# Bus_Definition_V1_2.net
KiCad netlist of a schematic drawn in EAGLE
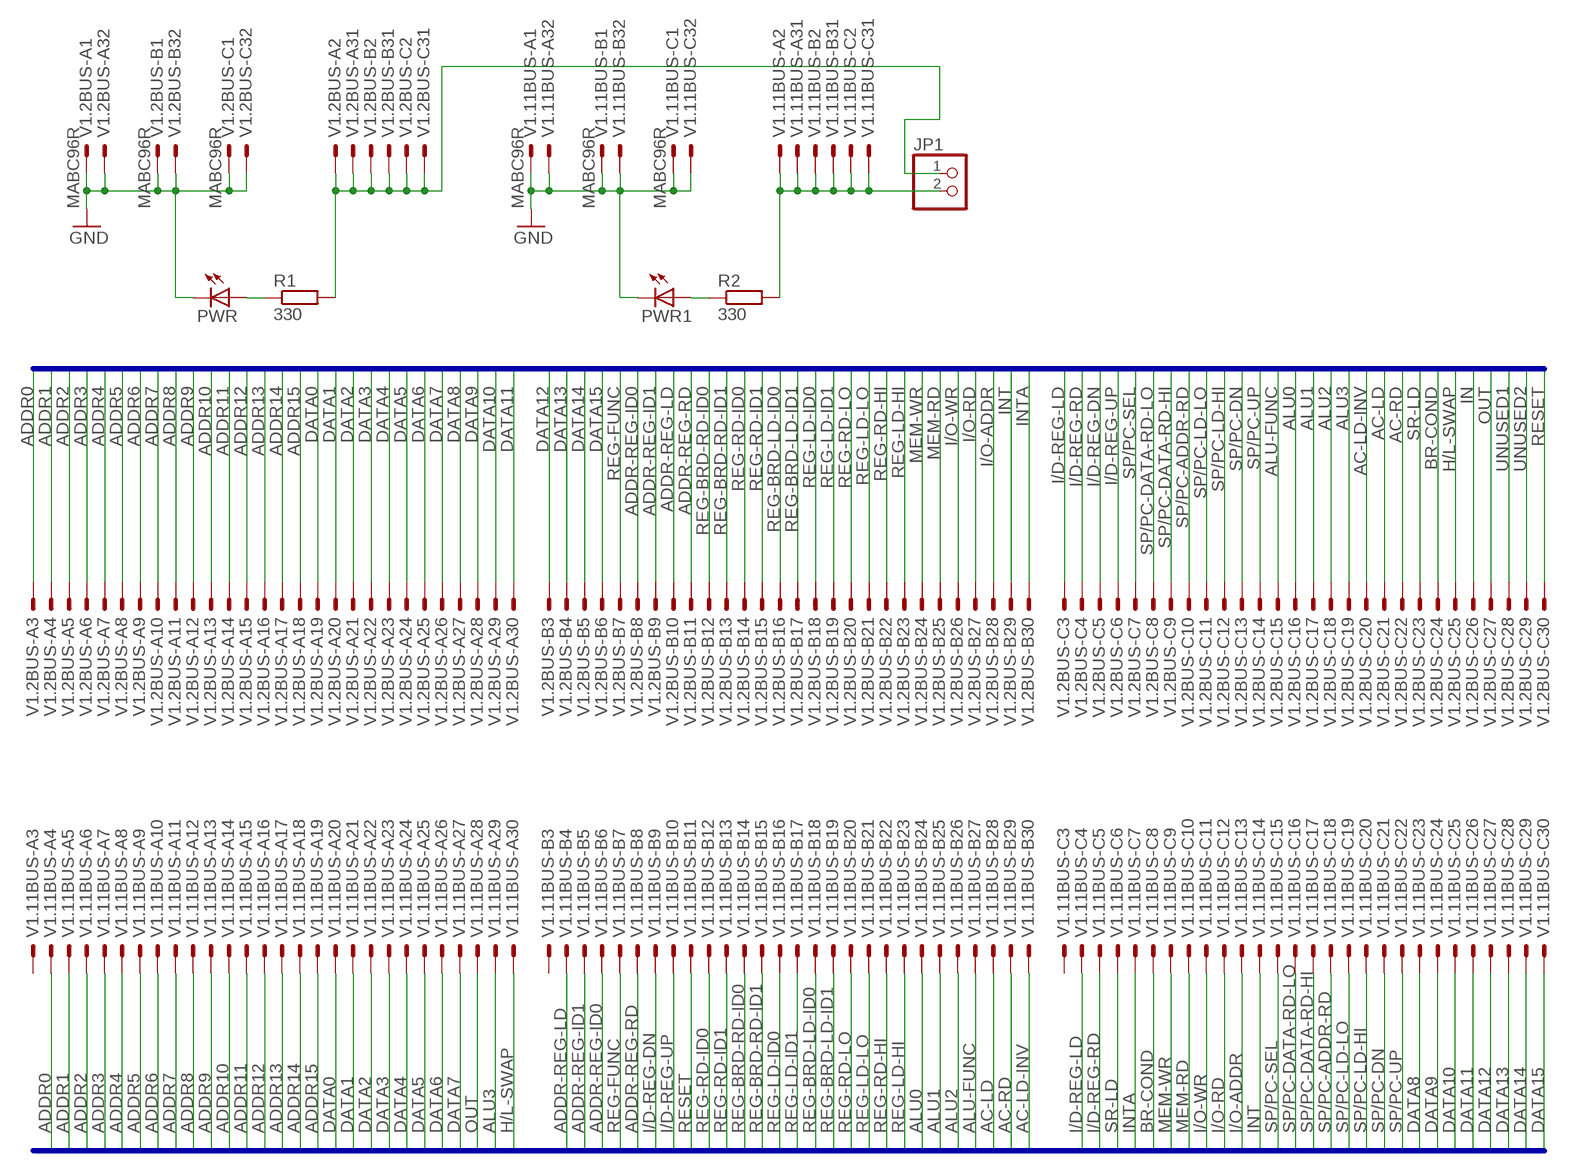
[diagram p0: schematic, sheet 1]

(export (version "E")
  (design (tool "Eeschema 10.0.6"))
  (components
    (comp (ref "JP1")
      (value "PINHD-1X2")
      (footprint "eagle-import:1X02")
      (libsource (lib "eagle-import") (part "PINHD-1X2"))
    )
    (comp (ref "PWR")
      (value "LED5MM")
      (footprint "eagle-import:LED5MM")
      (libsource (lib "eagle-import") (part "LED5MM"))
    )
    (comp (ref "PWR1")
      (value "LED5MM")
      (footprint "eagle-import:LED5MM")
      (libsource (lib "eagle-import") (part "LED5MM"))
    )
    (comp (ref "R1")
      (value "330")
      (footprint "eagle-import:0207_10")
      (libsource (lib "eagle-import") (part "R0207/10"))
    )
    (comp (ref "R2")
      (value "330")
      (footprint "eagle-import:0207_10")
      (libsource (lib "eagle-import") (part "R0207/10"))
    )
    (comp (ref "V1.2BUS")
      (value "MABC96R")
      (footprint "eagle-import:MABC96R")
      (libsource (lib "eagle-import") (part "MABC96R"))
    )
    (comp (ref "V1.11BUS")
      (value "MABC96R")
      (footprint "eagle-import:MABC96R")
      (libsource (lib "eagle-import") (part "MABC96R"))
    )
  )
  (nets
    (net (code "1") (name "/AC-LD") (class "Default")
      (node (ref "V1.11BUS") (pin "B28") (pinfunction "S_B28") (pintype "passive"))
      (node (ref "V1.2BUS") (pin "C21") (pinfunction "S_C21") (pintype "passive"))
    )
    (net (code "2") (name "/AC-LD-INV") (class "Default")
      (node (ref "V1.11BUS") (pin "B30") (pinfunction "S_B30") (pintype "passive"))
      (node (ref "V1.2BUS") (pin "C20") (pinfunction "S_C20") (pintype "passive"))
    )
    (net (code "3") (name "/AC-RD") (class "Default")
      (node (ref "V1.11BUS") (pin "B29") (pinfunction "S_B29") (pintype "passive"))
      (node (ref "V1.2BUS") (pin "C22") (pinfunction "S_C22") (pintype "passive"))
    )
    (net (code "4") (name "/ADDR-REG-ID0") (class "Default")
      (node (ref "V1.11BUS") (pin "B6") (pinfunction "S_B6") (pintype "passive"))
      (node (ref "V1.2BUS") (pin "B8") (pinfunction "S_B8") (pintype "passive"))
    )
    (net (code "5") (name "/ADDR-REG-ID1") (class "Default")
      (node (ref "V1.11BUS") (pin "B5") (pinfunction "S_B5") (pintype "passive"))
      (node (ref "V1.2BUS") (pin "B9") (pinfunction "S_B9") (pintype "passive"))
    )
    (net (code "6") (name "/ADDR-REG-LD") (class "Default")
      (node (ref "V1.11BUS") (pin "B4") (pinfunction "S_B4") (pintype "passive"))
      (node (ref "V1.2BUS") (pin "B10") (pinfunction "S_B10") (pintype "passive"))
    )
    (net (code "7") (name "/ADDR-REG-RD") (class "Default")
      (node (ref "V1.11BUS") (pin "B8") (pinfunction "S_B8") (pintype "passive"))
      (node (ref "V1.2BUS") (pin "B11") (pinfunction "S_B11") (pintype "passive"))
    )
    (net (code "8") (name "/ADDR0") (class "Default")
      (node (ref "V1.11BUS") (pin "A4") (pinfunction "S_A4") (pintype "passive"))
      (node (ref "V1.2BUS") (pin "A3") (pinfunction "S_A3") (pintype "passive"))
    )
    (net (code "9") (name "/ADDR1") (class "Default")
      (node (ref "V1.11BUS") (pin "A5") (pinfunction "S_A5") (pintype "passive"))
      (node (ref "V1.2BUS") (pin "A4") (pinfunction "S_A4") (pintype "passive"))
    )
    (net (code "10") (name "/ADDR2") (class "Default")
      (node (ref "V1.11BUS") (pin "A6") (pinfunction "S_A6") (pintype "passive"))
      (node (ref "V1.2BUS") (pin "A5") (pinfunction "S_A5") (pintype "passive"))
    )
    (net (code "11") (name "/ADDR3") (class "Default")
      (node (ref "V1.11BUS") (pin "A7") (pinfunction "S_A7") (pintype "passive"))
      (node (ref "V1.2BUS") (pin "A6") (pinfunction "S_A6") (pintype "passive"))
    )
    (net (code "12") (name "/ADDR4") (class "Default")
      (node (ref "V1.11BUS") (pin "A8") (pinfunction "S_A8") (pintype "passive"))
      (node (ref "V1.2BUS") (pin "A7") (pinfunction "S_A7") (pintype "passive"))
    )
    (net (code "13") (name "/ADDR5") (class "Default")
      (node (ref "V1.11BUS") (pin "A9") (pinfunction "S_A9") (pintype "passive"))
      (node (ref "V1.2BUS") (pin "A8") (pinfunction "S_A8") (pintype "passive"))
    )
    (net (code "14") (name "/ADDR6") (class "Default")
      (node (ref "V1.11BUS") (pin "A10") (pinfunction "S_A10") (pintype "passive"))
      (node (ref "V1.2BUS") (pin "A9") (pinfunction "S_A9") (pintype "passive"))
    )
    (net (code "15") (name "/ADDR7") (class "Default")
      (node (ref "V1.11BUS") (pin "A11") (pinfunction "S_A11") (pintype "passive"))
      (node (ref "V1.2BUS") (pin "A10") (pinfunction "S_A10") (pintype "passive"))
    )
    (net (code "16") (name "/ADDR8") (class "Default")
      (node (ref "V1.11BUS") (pin "A12") (pinfunction "S_A12") (pintype "passive"))
      (node (ref "V1.2BUS") (pin "A11") (pinfunction "S_A11") (pintype "passive"))
    )
    (net (code "17") (name "/ADDR9") (class "Default")
      (node (ref "V1.11BUS") (pin "A13") (pinfunction "S_A13") (pintype "passive"))
      (node (ref "V1.2BUS") (pin "A12") (pinfunction "S_A12") (pintype "passive"))
    )
    (net (code "18") (name "/ADDR10") (class "Default")
      (node (ref "V1.11BUS") (pin "A14") (pinfunction "S_A14") (pintype "passive"))
      (node (ref "V1.2BUS") (pin "A13") (pinfunction "S_A13") (pintype "passive"))
    )
    (net (code "19") (name "/ADDR11") (class "Default")
      (node (ref "V1.11BUS") (pin "A15") (pinfunction "S_A15") (pintype "passive"))
      (node (ref "V1.2BUS") (pin "A14") (pinfunction "S_A14") (pintype "passive"))
    )
    (net (code "20") (name "/ADDR12") (class "Default")
      (node (ref "V1.11BUS") (pin "A16") (pinfunction "S_A16") (pintype "passive"))
      (node (ref "V1.2BUS") (pin "A15") (pinfunction "S_A15") (pintype "passive"))
    )
    (net (code "21") (name "/ADDR13") (class "Default")
      (node (ref "V1.11BUS") (pin "A17") (pinfunction "S_A17") (pintype "passive"))
      (node (ref "V1.2BUS") (pin "A16") (pinfunction "S_A16") (pintype "passive"))
    )
    (net (code "22") (name "/ADDR14") (class "Default")
      (node (ref "V1.11BUS") (pin "A18") (pinfunction "S_A18") (pintype "passive"))
      (node (ref "V1.2BUS") (pin "A17") (pinfunction "S_A17") (pintype "passive"))
    )
    (net (code "23") (name "/ADDR15") (class "Default")
      (node (ref "V1.11BUS") (pin "A19") (pinfunction "S_A19") (pintype "passive"))
      (node (ref "V1.2BUS") (pin "A18") (pinfunction "S_A18") (pintype "passive"))
    )
    (net (code "24") (name "/ALU-FUNC") (class "Default")
      (node (ref "V1.11BUS") (pin "B27") (pinfunction "S_B27") (pintype "passive"))
      (node (ref "V1.2BUS") (pin "C15") (pinfunction "S_C15") (pintype "passive"))
    )
    (net (code "25") (name "/ALU0") (class "Default")
      (node (ref "V1.11BUS") (pin "B24") (pinfunction "S_B24") (pintype "passive"))
      (node (ref "V1.2BUS") (pin "C16") (pinfunction "S_C16") (pintype "passive"))
    )
    (net (code "26") (name "/ALU1") (class "Default")
      (node (ref "V1.11BUS") (pin "B25") (pinfunction "S_B25") (pintype "passive"))
      (node (ref "V1.2BUS") (pin "C17") (pinfunction "S_C17") (pintype "passive"))
    )
    (net (code "27") (name "/ALU2") (class "Default")
      (node (ref "V1.11BUS") (pin "B26") (pinfunction "S_B26") (pintype "passive"))
      (node (ref "V1.2BUS") (pin "C18") (pinfunction "S_C18") (pintype "passive"))
    )
    (net (code "28") (name "/ALU3") (class "Default")
      (node (ref "V1.11BUS") (pin "A29") (pinfunction "S_A29") (pintype "passive"))
      (node (ref "V1.2BUS") (pin "C19") (pinfunction "S_C19") (pintype "passive"))
    )
    (net (code "29") (name "/BR-COND") (class "Default")
      (node (ref "V1.11BUS") (pin "C8") (pinfunction "S_C8") (pintype "passive"))
      (node (ref "V1.2BUS") (pin "C24") (pinfunction "S_C24") (pintype "passive"))
    )
    (net (code "30") (name "/DATA0") (class "Default")
      (node (ref "V1.11BUS") (pin "A20") (pinfunction "S_A20") (pintype "passive"))
      (node (ref "V1.2BUS") (pin "A19") (pinfunction "S_A19") (pintype "passive"))
    )
    (net (code "31") (name "/DATA1") (class "Default")
      (node (ref "V1.11BUS") (pin "A21") (pinfunction "S_A21") (pintype "passive"))
      (node (ref "V1.2BUS") (pin "A20") (pinfunction "S_A20") (pintype "passive"))
    )
    (net (code "32") (name "/DATA2") (class "Default")
      (node (ref "V1.11BUS") (pin "A22") (pinfunction "S_A22") (pintype "passive"))
      (node (ref "V1.2BUS") (pin "A21") (pinfunction "S_A21") (pintype "passive"))
    )
    (net (code "33") (name "/DATA3") (class "Default")
      (node (ref "V1.11BUS") (pin "A23") (pinfunction "S_A23") (pintype "passive"))
      (node (ref "V1.2BUS") (pin "A22") (pinfunction "S_A22") (pintype "passive"))
    )
    (net (code "34") (name "/DATA4") (class "Default")
      (node (ref "V1.11BUS") (pin "A24") (pinfunction "S_A24") (pintype "passive"))
      (node (ref "V1.2BUS") (pin "A23") (pinfunction "S_A23") (pintype "passive"))
    )
    (net (code "35") (name "/DATA5") (class "Default")
      (node (ref "V1.11BUS") (pin "A25") (pinfunction "S_A25") (pintype "passive"))
      (node (ref "V1.2BUS") (pin "A24") (pinfunction "S_A24") (pintype "passive"))
    )
    (net (code "36") (name "/DATA6") (class "Default")
      (node (ref "V1.11BUS") (pin "A26") (pinfunction "S_A26") (pintype "passive"))
      (node (ref "V1.2BUS") (pin "A25") (pinfunction "S_A25") (pintype "passive"))
    )
    (net (code "37") (name "/DATA7") (class "Default")
      (node (ref "V1.11BUS") (pin "A27") (pinfunction "S_A27") (pintype "passive"))
      (node (ref "V1.2BUS") (pin "A26") (pinfunction "S_A26") (pintype "passive"))
    )
    (net (code "38") (name "/DATA8") (class "Default")
      (node (ref "V1.11BUS") (pin "C23") (pinfunction "S_C23") (pintype "passive"))
      (node (ref "V1.2BUS") (pin "A27") (pinfunction "S_A27") (pintype "passive"))
    )
    (net (code "39") (name "/DATA9") (class "Default")
      (node (ref "V1.11BUS") (pin "C24") (pinfunction "S_C24") (pintype "passive"))
      (node (ref "V1.2BUS") (pin "A28") (pinfunction "S_A28") (pintype "passive"))
    )
    (net (code "40") (name "/DATA10") (class "Default")
      (node (ref "V1.11BUS") (pin "C25") (pinfunction "S_C25") (pintype "passive"))
      (node (ref "V1.2BUS") (pin "A29") (pinfunction "S_A29") (pintype "passive"))
    )
    (net (code "41") (name "/DATA11") (class "Default")
      (node (ref "V1.11BUS") (pin "C26") (pinfunction "S_C26") (pintype "passive"))
      (node (ref "V1.2BUS") (pin "A30") (pinfunction "S_A30") (pintype "passive"))
    )
    (net (code "42") (name "/DATA12") (class "Default")
      (node (ref "V1.11BUS") (pin "C27") (pinfunction "S_C27") (pintype "passive"))
      (node (ref "V1.2BUS") (pin "B3") (pinfunction "S_B3") (pintype "passive"))
    )
    (net (code "43") (name "/DATA13") (class "Default")
      (node (ref "V1.11BUS") (pin "C28") (pinfunction "S_C28") (pintype "passive"))
      (node (ref "V1.2BUS") (pin "B4") (pinfunction "S_B4") (pintype "passive"))
    )
    (net (code "44") (name "/DATA14") (class "Default")
      (node (ref "V1.11BUS") (pin "C29") (pinfunction "S_C29") (pintype "passive"))
      (node (ref "V1.2BUS") (pin "B5") (pinfunction "S_B5") (pintype "passive"))
    )
    (net (code "45") (name "/DATA15") (class "Default")
      (node (ref "V1.11BUS") (pin "C30") (pinfunction "S_C30") (pintype "passive"))
      (node (ref "V1.2BUS") (pin "B6") (pinfunction "S_B6") (pintype "passive"))
    )
    (net (code "46") (name "/H{slash}L-SWAP") (class "Default")
      (node (ref "V1.11BUS") (pin "A30") (pinfunction "S_A30") (pintype "passive"))
      (node (ref "V1.2BUS") (pin "C25") (pinfunction "S_C25") (pintype "passive"))
    )
    (net (code "47") (name "/IN") (class "Default")
      (node (ref "V1.2BUS") (pin "C26") (pinfunction "S_C26") (pintype "passive"))
    )
    (net (code "48") (name "/INT") (class "Default")
      (node (ref "V1.11BUS") (pin "C14") (pinfunction "S_C14") (pintype "passive"))
      (node (ref "V1.2BUS") (pin "B29") (pinfunction "S_B29") (pintype "passive"))
    )
    (net (code "49") (name "/INTA") (class "Default")
      (node (ref "V1.11BUS") (pin "C7") (pinfunction "S_C7") (pintype "passive"))
      (node (ref "V1.2BUS") (pin "B30") (pinfunction "S_B30") (pintype "passive"))
    )
    (net (code "50") (name "/I{slash}D-REG-DN") (class "Default")
      (node (ref "V1.11BUS") (pin "B9") (pinfunction "S_B9") (pintype "passive"))
      (node (ref "V1.2BUS") (pin "C5") (pinfunction "S_C5") (pintype "passive"))
    )
    (net (code "51") (name "/I{slash}D-REG-LD") (class "Default")
      (node (ref "V1.11BUS") (pin "C4") (pinfunction "S_C4") (pintype "passive"))
      (node (ref "V1.2BUS") (pin "C3") (pinfunction "S_C3") (pintype "passive"))
    )
    (net (code "52") (name "/I{slash}D-REG-RD") (class "Default")
      (node (ref "V1.11BUS") (pin "C5") (pinfunction "S_C5") (pintype "passive"))
      (node (ref "V1.2BUS") (pin "C4") (pinfunction "S_C4") (pintype "passive"))
    )
    (net (code "53") (name "/I{slash}D-REG-UP") (class "Default")
      (node (ref "V1.11BUS") (pin "B10") (pinfunction "S_B10") (pintype "passive"))
      (node (ref "V1.2BUS") (pin "C6") (pinfunction "S_C6") (pintype "passive"))
    )
    (net (code "54") (name "/I{slash}O-ADDR") (class "Default")
      (node (ref "V1.11BUS") (pin "C13") (pinfunction "S_C13") (pintype "passive"))
      (node (ref "V1.2BUS") (pin "B28") (pinfunction "S_B28") (pintype "passive"))
    )
    (net (code "55") (name "/I{slash}O-RD") (class "Default")
      (node (ref "V1.11BUS") (pin "C12") (pinfunction "S_C12") (pintype "passive"))
      (node (ref "V1.2BUS") (pin "B27") (pinfunction "S_B27") (pintype "passive"))
    )
    (net (code "56") (name "/I{slash}O-WR") (class "Default")
      (node (ref "V1.11BUS") (pin "C11") (pinfunction "S_C11") (pintype "passive"))
      (node (ref "V1.2BUS") (pin "B26") (pinfunction "S_B26") (pintype "passive"))
    )
    (net (code "57") (name "/MEM-RD") (class "Default")
      (node (ref "V1.11BUS") (pin "C10") (pinfunction "S_C10") (pintype "passive"))
      (node (ref "V1.2BUS") (pin "B25") (pinfunction "S_B25") (pintype "passive"))
    )
    (net (code "58") (name "/MEM-WR") (class "Default")
      (node (ref "V1.11BUS") (pin "C9") (pinfunction "S_C9") (pintype "passive"))
      (node (ref "V1.2BUS") (pin "B24") (pinfunction "S_B24") (pintype "passive"))
    )
    (net (code "59") (name "/OUT") (class "Default")
      (node (ref "V1.11BUS") (pin "A28") (pinfunction "S_A28") (pintype "passive"))
      (node (ref "V1.2BUS") (pin "C27") (pinfunction "S_C27") (pintype "passive"))
    )
    (net (code "60") (name "/REG-BRD-LD-ID0") (class "Default")
      (node (ref "V1.11BUS") (pin "B18") (pinfunction "S_B18") (pintype "passive"))
      (node (ref "V1.2BUS") (pin "B16") (pinfunction "S_B16") (pintype "passive"))
    )
    (net (code "61") (name "/REG-BRD-LD-ID1") (class "Default")
      (node (ref "V1.11BUS") (pin "B19") (pinfunction "S_B19") (pintype "passive"))
      (node (ref "V1.2BUS") (pin "B17") (pinfunction "S_B17") (pintype "passive"))
    )
    (net (code "62") (name "/REG-BRD-RD-ID0") (class "Default")
      (node (ref "V1.11BUS") (pin "B14") (pinfunction "S_B14") (pintype "passive"))
      (node (ref "V1.2BUS") (pin "B12") (pinfunction "S_B12") (pintype "passive"))
    )
    (net (code "63") (name "/REG-BRD-RD-ID1") (class "Default")
      (node (ref "V1.11BUS") (pin "B15") (pinfunction "S_B15") (pintype "passive"))
      (node (ref "V1.2BUS") (pin "B13") (pinfunction "S_B13") (pintype "passive"))
    )
    (net (code "64") (name "/REG-FUNC") (class "Default")
      (node (ref "V1.11BUS") (pin "B7") (pinfunction "S_B7") (pintype "passive"))
      (node (ref "V1.2BUS") (pin "B7") (pinfunction "S_B7") (pintype "passive"))
    )
    (net (code "65") (name "/REG-LD-HI") (class "Default")
      (node (ref "V1.11BUS") (pin "B23") (pinfunction "S_B23") (pintype "passive"))
      (node (ref "V1.2BUS") (pin "B23") (pinfunction "S_B23") (pintype "passive"))
    )
    (net (code "66") (name "/REG-LD-ID0") (class "Default")
      (node (ref "V1.11BUS") (pin "B16") (pinfunction "S_B16") (pintype "passive"))
      (node (ref "V1.2BUS") (pin "B18") (pinfunction "S_B18") (pintype "passive"))
    )
    (net (code "67") (name "/REG-LD-ID1") (class "Default")
      (node (ref "V1.11BUS") (pin "B17") (pinfunction "S_B17") (pintype "passive"))
      (node (ref "V1.2BUS") (pin "B19") (pinfunction "S_B19") (pintype "passive"))
    )
    (net (code "68") (name "/REG-LD-LO") (class "Default")
      (node (ref "V1.11BUS") (pin "B21") (pinfunction "S_B21") (pintype "passive"))
      (node (ref "V1.2BUS") (pin "B21") (pinfunction "S_B21") (pintype "passive"))
    )
    (net (code "69") (name "/REG-RD-HI") (class "Default")
      (node (ref "V1.11BUS") (pin "B22") (pinfunction "S_B22") (pintype "passive"))
      (node (ref "V1.2BUS") (pin "B22") (pinfunction "S_B22") (pintype "passive"))
    )
    (net (code "70") (name "/REG-RD-ID0") (class "Default")
      (node (ref "V1.11BUS") (pin "B12") (pinfunction "S_B12") (pintype "passive"))
      (node (ref "V1.2BUS") (pin "B14") (pinfunction "S_B14") (pintype "passive"))
    )
    (net (code "71") (name "/REG-RD-ID1") (class "Default")
      (node (ref "V1.11BUS") (pin "B13") (pinfunction "S_B13") (pintype "passive"))
      (node (ref "V1.2BUS") (pin "B15") (pinfunction "S_B15") (pintype "passive"))
    )
    (net (code "72") (name "/REG-RD-LO") (class "Default")
      (node (ref "V1.11BUS") (pin "B20") (pinfunction "S_B20") (pintype "passive"))
      (node (ref "V1.2BUS") (pin "B20") (pinfunction "S_B20") (pintype "passive"))
    )
    (net (code "73") (name "/RESET") (class "Default")
      (node (ref "V1.11BUS") (pin "B11") (pinfunction "S_B11") (pintype "passive"))
      (node (ref "V1.2BUS") (pin "C30") (pinfunction "S_C30") (pintype "passive"))
    )
    (net (code "74") (name "/SP{slash}PC-ADDR-RD") (class "Default")
      (node (ref "V1.11BUS") (pin "C18") (pinfunction "S_C18") (pintype "passive"))
      (node (ref "V1.2BUS") (pin "C10") (pinfunction "S_C10") (pintype "passive"))
    )
    (net (code "75") (name "/SP{slash}PC-DATA-RD-HI") (class "Default")
      (node (ref "V1.11BUS") (pin "C17") (pinfunction "S_C17") (pintype "passive"))
      (node (ref "V1.2BUS") (pin "C9") (pinfunction "S_C9") (pintype "passive"))
    )
    (net (code "76") (name "/SP{slash}PC-DATA-RD-LO") (class "Default")
      (node (ref "V1.11BUS") (pin "C16") (pinfunction "S_C16") (pintype "passive"))
      (node (ref "V1.2BUS") (pin "C8") (pinfunction "S_C8") (pintype "passive"))
    )
    (net (code "77") (name "/SP{slash}PC-DN") (class "Default")
      (node (ref "V1.11BUS") (pin "C21") (pinfunction "S_C21") (pintype "passive"))
      (node (ref "V1.2BUS") (pin "C13") (pinfunction "S_C13") (pintype "passive"))
    )
    (net (code "78") (name "/SP{slash}PC-LD-HI") (class "Default")
      (node (ref "V1.11BUS") (pin "C20") (pinfunction "S_C20") (pintype "passive"))
      (node (ref "V1.2BUS") (pin "C12") (pinfunction "S_C12") (pintype "passive"))
    )
    (net (code "79") (name "/SP{slash}PC-LD-LO") (class "Default")
      (node (ref "V1.11BUS") (pin "C19") (pinfunction "S_C19") (pintype "passive"))
      (node (ref "V1.2BUS") (pin "C11") (pinfunction "S_C11") (pintype "passive"))
    )
    (net (code "80") (name "/SP{slash}PC-SEL") (class "Default")
      (node (ref "V1.11BUS") (pin "C15") (pinfunction "S_C15") (pintype "passive"))
      (node (ref "V1.2BUS") (pin "C7") (pinfunction "S_C7") (pintype "passive"))
    )
    (net (code "81") (name "/SP{slash}PC-UP") (class "Default")
      (node (ref "V1.11BUS") (pin "C22") (pinfunction "S_C22") (pintype "passive"))
      (node (ref "V1.2BUS") (pin "C14") (pinfunction "S_C14") (pintype "passive"))
    )
    (net (code "82") (name "/SR-LD") (class "Default")
      (node (ref "V1.11BUS") (pin "C6") (pinfunction "S_C6") (pintype "passive"))
      (node (ref "V1.2BUS") (pin "C23") (pinfunction "S_C23") (pintype "passive"))
    )
    (net (code "83") (name "/UNUSED1") (class "Default")
      (node (ref "V1.2BUS") (pin "C28") (pinfunction "S_C28") (pintype "passive"))
    )
    (net (code "84") (name "/UNUSED2") (class "Default")
      (node (ref "V1.2BUS") (pin "C29") (pinfunction "S_C29") (pintype "passive"))
    )
    (net (code "86") (name "GND") (class "Default")
      (node (ref "PWR") (pin "K") (pinfunction "C_K") (pintype "passive"))
      (node (ref "PWR1") (pin "K") (pinfunction "C_K") (pintype "passive"))
      (node (ref "V1.11BUS") (pin "A1") (pinfunction "S_A1") (pintype "passive"))
      (node (ref "V1.11BUS") (pin "A32") (pinfunction "S_A32") (pintype "passive"))
      (node (ref "V1.11BUS") (pin "B1") (pinfunction "S_B1") (pintype "passive"))
      (node (ref "V1.11BUS") (pin "B32") (pinfunction "S_B32") (pintype "passive"))
      (node (ref "V1.11BUS") (pin "C1") (pinfunction "S_C1") (pintype "passive"))
      (node (ref "V1.11BUS") (pin "C32") (pinfunction "S_C32") (pintype "passive"))
      (node (ref "V1.2BUS") (pin "A1") (pinfunction "S_A1") (pintype "passive"))
      (node (ref "V1.2BUS") (pin "A32") (pinfunction "S_A32") (pintype "passive"))
      (node (ref "V1.2BUS") (pin "B1") (pinfunction "S_B1") (pintype "passive"))
      (node (ref "V1.2BUS") (pin "B32") (pinfunction "S_B32") (pintype "passive"))
      (node (ref "V1.2BUS") (pin "C1") (pinfunction "S_C1") (pintype "passive"))
      (node (ref "V1.2BUS") (pin "C32") (pinfunction "S_C32") (pintype "passive"))
    )
    (net (code "87") (name "Net-(PWR-PadA)") (class "Default")
      (node (ref "PWR") (pin "A") (pinfunction "A_A") (pintype "passive"))
      (node (ref "R1") (pin "1") (pinfunction "1_1") (pintype "passive"))
    )
    (net (code "88") (name "Net-(PWR1-PadA)") (class "Default")
      (node (ref "PWR1") (pin "A") (pinfunction "A_A") (pintype "passive"))
      (node (ref "R2") (pin "1") (pinfunction "1_1") (pintype "passive"))
    )
    (net (code "89") (name "Net-(V1.2BUSAR-S)") (class "Default")
      (node (ref "JP1") (pin "1") (pinfunction "1_1") (pintype "passive"))
      (node (ref "R1") (pin "2") (pinfunction "2_2") (pintype "passive"))
      (node (ref "V1.2BUS") (pin "A2") (pinfunction "S_A2") (pintype "passive"))
      (node (ref "V1.2BUS") (pin "A31") (pinfunction "S_A31") (pintype "passive"))
      (node (ref "V1.2BUS") (pin "B2") (pinfunction "S_B2") (pintype "passive"))
      (node (ref "V1.2BUS") (pin "B31") (pinfunction "S_B31") (pintype "passive"))
      (node (ref "V1.2BUS") (pin "C2") (pinfunction "S_C2") (pintype "passive"))
      (node (ref "V1.2BUS") (pin "C31") (pinfunction "S_C31") (pintype "passive"))
    )
    (net (code "90") (name "Net-(V1.11BUSAR-S)") (class "Default")
      (node (ref "JP1") (pin "2") (pinfunction "2_2") (pintype "passive"))
      (node (ref "R2") (pin "2") (pinfunction "2_2") (pintype "passive"))
      (node (ref "V1.11BUS") (pin "A2") (pinfunction "S_A2") (pintype "passive"))
      (node (ref "V1.11BUS") (pin "A31") (pinfunction "S_A31") (pintype "passive"))
      (node (ref "V1.11BUS") (pin "B2") (pinfunction "S_B2") (pintype "passive"))
      (node (ref "V1.11BUS") (pin "B31") (pinfunction "S_B31") (pintype "passive"))
      (node (ref "V1.11BUS") (pin "C2") (pinfunction "S_C2") (pintype "passive"))
      (node (ref "V1.11BUS") (pin "C31") (pinfunction "S_C31") (pintype "passive"))
    )
    (net (code "91") (name "unconnected-(V1.11BUSBC-S-PadB3)") (class "Default")
      (node (ref "V1.11BUS") (pin "B3") (pinfunction "S_B3") (pintype "passive"))
    )
    (net (code "92") (name "unconnected-(V1.11BUSCI-S-PadC3)") (class "Default")
      (node (ref "V1.11BUS") (pin "C3") (pinfunction "S_C3") (pintype "passive"))
    )
    (net (code "93") (name "unconnected-(V1.11BUSW-S-PadA3)") (class "Default")
      (node (ref "V1.11BUS") (pin "A3") (pinfunction "S_A3") (pintype "passive"))
    )
  )
)
